# Encoder.net
KiCad netlist of a schematic drawn in Altium Designer
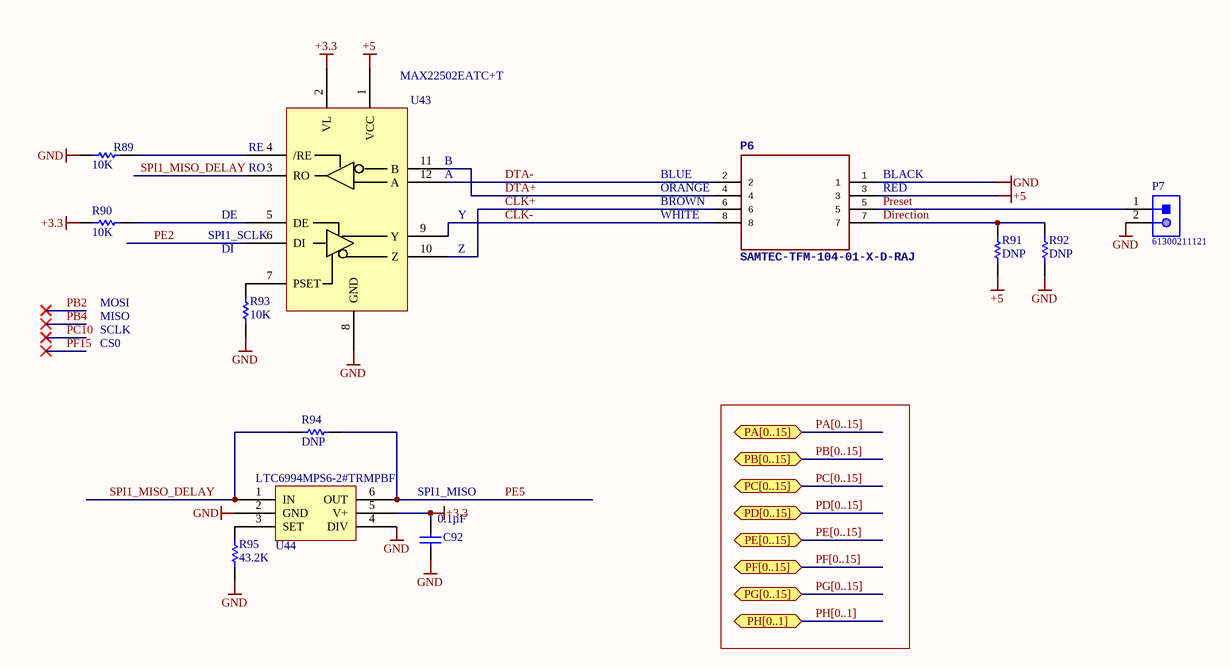
[diagram p0: Encoder.SchDoc]

(export (version "E")
  (design (tool "Eeschema 10.0.6"))
  (components
    (comp (ref "C92")
      (value "CAP CER 0.1UF 25V X7R 0805")
      (footprint "CAPC0805(2012)145_N")
      (fields
        (field (name "MANUFACTURER") "Murata Electronics North America")
        (field (name "MANUFACTURER PART NUMBER") "GRM21BR71E104KA01L")
        (field (name "CAPACITANCE") "0.1µF")
        (field (name "TOLERANCE") "±10%")
      )
      (libsource (lib "Altium Content Vault") (part "CMP-1036-04795-1"))
    )
    (comp (ref "P6")
      (value "SAMTEC-TFM-104-01-X-D-RAJ")
      (footprint "SAMTEC-TFM-104-01-X-D-RA")
      (libsource (lib "SAMTEC-TFM-104-01-X-D-RA") (part "SAMTEC-TFM-104-01-X-D-RAJ"))
    )
    (comp (ref "P7")
      (value "61300211121")
      (footprint "61300211121")
      (description "THT Vertical Pin Header WR-PHD, Pitch 2.54 mm, Single Row, 2 pins")
      (fields (field (name "MANUFACTURER") "Wurth Elektronik") (field (name "PUBLISHER") "WurthElektronik"))
      (libsource (lib "Altium Content Vault") (part "WE-CN-1P-M-R2"))
    )
    (comp (ref "R89")
      (value "10K")
      (footprint "RESC0805(2012)_L")
      (description "RES SMD 10K OHM 1% 1/8W 0805")
      (fields
        (field (name "MANUFACTURER") "Vishay Dale")
        (field (name "MANUFACTURER PART NUMBER") "CRCW080510K0FKEA")
      )
      (libsource (lib "Altium Content Vault") (part "CMP-1013-00215-1"))
    )
    (comp (ref "R90")
      (value "10K")
      (footprint "RESC0805(2012)_L")
      (description "RES SMD 10K OHM 1% 1/8W 0805")
      (fields
        (field (name "MANUFACTURER") "Vishay Dale")
        (field (name "MANUFACTURER PART NUMBER") "CRCW080510K0FKEA")
      )
      (libsource (lib "Altium Content Vault") (part "CMP-1013-00215-1"))
    )
    (comp (ref "R91")
      (value "DNP")
      (footprint "RESC0805(2012)_L")
      (description "RES SMD 0 OHM 5% 1/8W 0805")
      (libsource (lib "Altium Content Vault") (part "CMP-1013-00215-1"))
    )
    (comp (ref "R92")
      (value "DNP")
      (footprint "RESC0805(2012)_L")
      (description "RES SMD 0 OHM 5% 1/8W 0805")
      (libsource (lib "Altium Content Vault") (part "CMP-1013-00215-1"))
    )
    (comp (ref "R93")
      (value "10K")
      (footprint "RESC0805(2012)_L")
      (description "RES SMD 10K OHM 1% 1/8W 0805")
      (fields
        (field (name "MANUFACTURER") "Vishay Dale")
        (field (name "MANUFACTURER PART NUMBER") "CRCW080510K0FKEA")
      )
      (libsource (lib "Altium Content Vault") (part "CMP-1013-00215-1"))
    )
    (comp (ref "R94")
      (value "DNP")
      (footprint "RESC0805(2012)_L")
      (description "RES SMD 0 OHM 5% 1/8W 0805")
      (libsource (lib "Altium Content Vault") (part "CMP-1013-00215-1"))
    )
    (comp (ref "R95")
      (value "43.2K")
      (footprint "RESC0805(2012)_L")
      (description "RES SMD 43.2K OHM 1% 1/8W 0805")
      (fields
        (field (name "MANUFACTURER") "Vishay Dale")
        (field (name "MANUFACTURER PART NUMBER") "CRCW080543K2FKEA")
      )
      (libsource (lib "Altium Content Vault") (part "CMP-1013-00215-1"))
    )
    (comp (ref "U43")
      (value "MAX22502EATC+T")
      (footprint "MAX22502EATC+T")
      (libsource (lib "ZLS_Schematic_lib") (part "MAX22502EATC+T"))
    )
    (comp (ref "U44")
      (value "LTC6994MPS6-2#TRMPBF")
      (footprint "LTC6994MPS6-2#TRMPBF")
      (fields
        (field (name "MANUFACTURER") "Linear Technology/Analog Devices")
        (field (name "MANUFACTURER PART NUMBER") "LTC6994CS6-2#TRMPBF")
        (field (name "BASE PART NUMBER") "LTC6994")
      )
      (libsource (lib "ZLS_Schematic_lib") (part "LTC6994MPS6-2#TRMPBF"))
    )
  )
  (nets
    (net (code "109") (name "+3.3") (class "Default")
      (node (ref "C92") (pin "1") (pinfunction "1_1") (pintype "passive"))
      (node (ref "R90") (pin "2") (pinfunction "2_2") (pintype "passive"))
      (node (ref "U43") (pin "2") (pinfunction "VL_2") (pintype "passive"))
      (node (ref "U44") (pin "5") (pinfunction "V+_5") (pintype "passive"))
    )
    (net (code "110") (name "+5") (class "Default")
      (node (ref "P6") (pin "3") (pinfunction "3_3") (pintype "passive"))
      (node (ref "R91") (pin "1") (pinfunction "1_1") (pintype "passive"))
      (node (ref "U43") (pin "1") (pinfunction "VCC_1") (pintype "passive"))
    )
    (net (code "111") (name "/CLK+") (class "Default")
      (node (ref "P6") (pin "6") (pinfunction "6_6") (pintype "passive"))
      (node (ref "U43") (pin "10") (pinfunction "Z_10") (pintype "passive"))
    )
    (net (code "112") (name "/CLK-") (class "Default")
      (node (ref "P6") (pin "8") (pinfunction "8_8") (pintype "passive"))
      (node (ref "U43") (pin "9") (pinfunction "Y_9") (pintype "passive"))
    )
    (net (code "113") (name "/DTA+") (class "Default")
      (node (ref "P6") (pin "4") (pinfunction "4_4") (pintype "passive"))
      (node (ref "U43") (pin "11") (pinfunction "B_11") (pintype "passive"))
    )
    (net (code "114") (name "/DTA-") (class "Default")
      (node (ref "P6") (pin "2") (pinfunction "2_2") (pintype "passive"))
      (node (ref "U43") (pin "12") (pinfunction "A_12") (pintype "passive"))
    )
    (net (code "115") (name "/Direction") (class "Default")
      (node (ref "P6") (pin "7") (pinfunction "7_7") (pintype "passive"))
      (node (ref "R91") (pin "2") (pinfunction "2_2") (pintype "passive"))
      (node (ref "R92") (pin "2") (pinfunction "2_2") (pintype "passive"))
    )
    (net (code "123") (name "/PE2") (class "Default")
      (node (ref "U43") (pin "6") (pinfunction "DI_6") (pintype "passive"))
    )
    (net (code "124") (name "/PE5") (class "Default")
      (node (ref "R94") (pin "2") (pinfunction "2_2") (pintype "passive"))
      (node (ref "U44") (pin "6") (pinfunction "OUT_6") (pintype "passive"))
    )
    (net (code "130") (name "/Preset") (class "Default")
      (node (ref "P6") (pin "5") (pinfunction "5_5") (pintype "passive"))
      (node (ref "P7") (pin "1") (pinfunction "1_1") (pintype "passive"))
    )
    (net (code "131") (name "/SPI1_MISO_DELAY") (class "Default")
      (node (ref "R94") (pin "1") (pinfunction "1_1") (pintype "passive"))
      (node (ref "U43") (pin "3") (pinfunction "RO_3") (pintype "passive"))
      (node (ref "U44") (pin "1") (pinfunction "IN_1") (pintype "passive"))
    )
    (net (code "132") (name "GND") (class "Default")
      (node (ref "C92") (pin "2") (pinfunction "2_2") (pintype "passive"))
      (node (ref "P6") (pin "1") (pinfunction "1_1") (pintype "passive"))
      (node (ref "P7") (pin "2") (pinfunction "2_2") (pintype "passive"))
      (node (ref "R89") (pin "2") (pinfunction "2_2") (pintype "passive"))
      (node (ref "R92") (pin "1") (pinfunction "1_1") (pintype "passive"))
      (node (ref "R93") (pin "2") (pinfunction "2_2") (pintype "passive"))
      (node (ref "R95") (pin "2") (pinfunction "2_2") (pintype "passive"))
      (node (ref "U43") (pin "8") (pinfunction "GND_8") (pintype "passive"))
      (node (ref "U44") (pin "2") (pinfunction "GND_2") (pintype "passive"))
      (node (ref "U44") (pin "4") (pinfunction "DIV_4") (pintype "passive"))
    )
    (net (code "133") (name "Net-(U43-DE)") (class "Default")
      (node (ref "R90") (pin "1") (pinfunction "1_1") (pintype "passive"))
      (node (ref "U43") (pin "5") (pinfunction "DE_5") (pintype "passive"))
    )
    (net (code "134") (name "Net-(U43-PSET)") (class "Default")
      (node (ref "R93") (pin "1") (pinfunction "1_1") (pintype "passive"))
      (node (ref "U43") (pin "7") (pinfunction "PSET_7") (pintype "passive"))
    )
    (net (code "135") (name "Net-(U43-{slash}RE)") (class "Default")
      (node (ref "R89") (pin "1") (pinfunction "1_1") (pintype "passive"))
      (node (ref "U43") (pin "4") (pinfunction "/RE_4") (pintype "passive"))
    )
    (net (code "136") (name "Net-(U44-SET)") (class "Default")
      (node (ref "R95") (pin "1") (pinfunction "1_1") (pintype "passive"))
      (node (ref "U44") (pin "3") (pinfunction "SET_3") (pintype "passive"))
    )
  )
)
